# MPU6050.net
KiCad netlist of a schematic drawn in Altium Designer
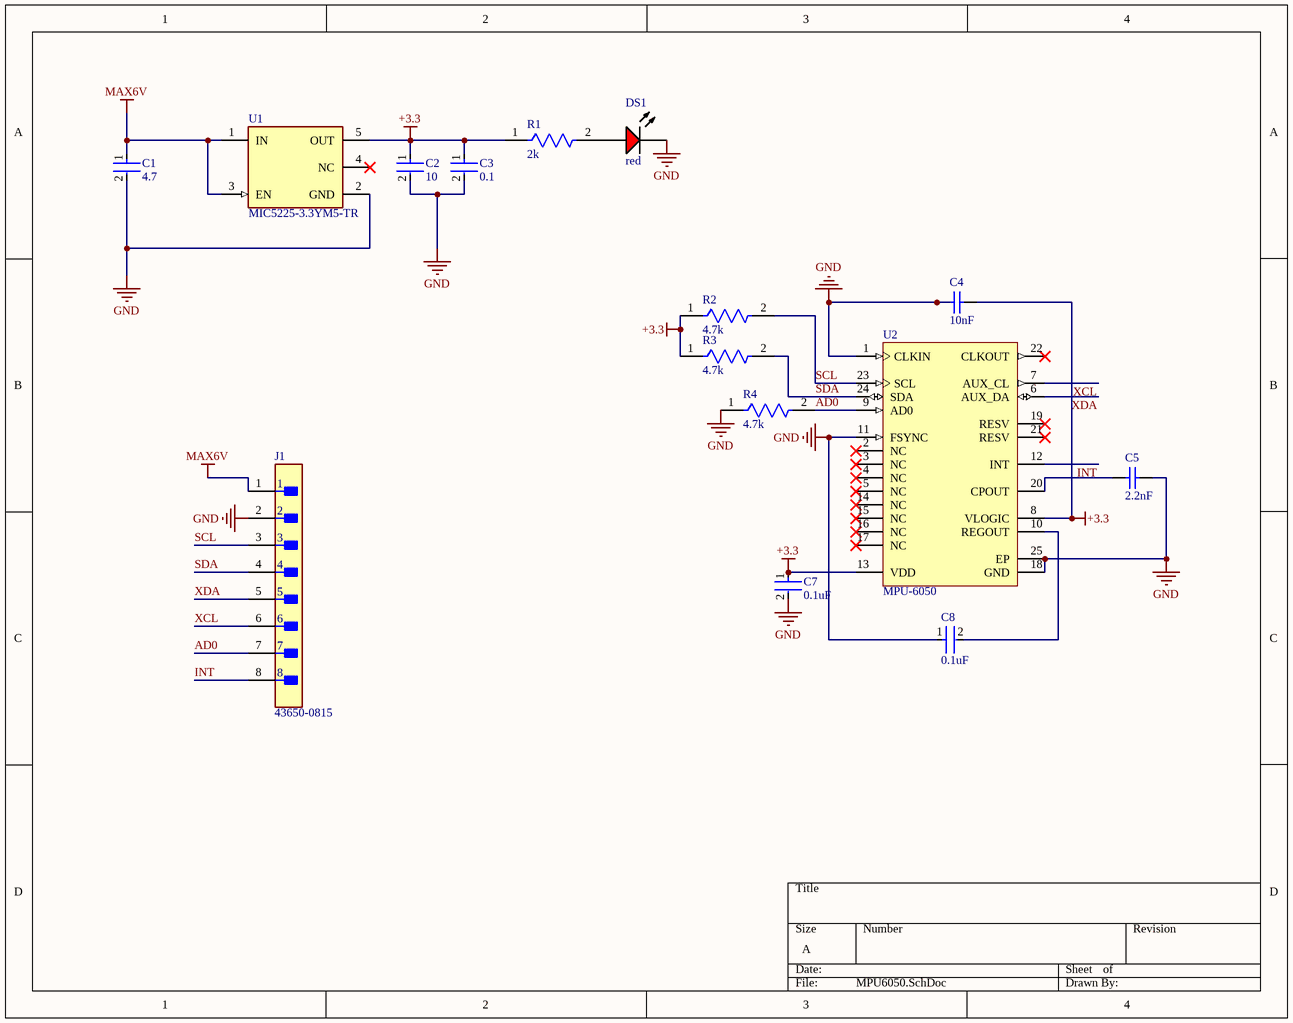
[diagram p0: MPU6050.SchDoc]

(export (version "E")
  (design (tool "Eeschema 10.0.6"))
  (components
    (comp (ref "C1")
      (value "4.7")
      (footprint "FP-C0805C475K8PACTU-MFG")
      (description "CAP CER 4.7UF 10V X5R 0805")
      (fields (field (name "TOLERANCE") "10%") (field (name "VOLTAGE") "10V"))
      (libsource (lib "Altium Content Vault") (part "e9c51b7dd13d4faca003ae77663ab08"))
    )
    (comp (ref "C2")
      (value "10")
      (footprint "FP-GRM21B-0_15-IPC_C")
      (description "Chip Multilayer Ceramic Capacitors for General Purpose, 0805, 10uF, X5R, 15%, 10%, 25V")
      (fields (field (name "VOLTAGE") "25V") (field (name "TOLERANCE") "10%"))
      (libsource (lib "Altium Content Vault") (part "b4654b650e69147ec39a6b967a45e02"))
    )
    (comp (ref "C3")
      (value "0.1")
      (footprint "FP-GCM155-0_05-IPC_C")
      (description "Ceramic Capacitor for Automotive 100nF ±10% 16VDC X7R 0402 Paper T/R")
      (fields (field (name "VOLTAGE") "16V") (field (name "TOLERANCE") "10%"))
      (libsource (lib "Altium Content Vault") (part "02cd4be3c70576c341d710602a673aa"))
    )
    (comp (ref "C4")
      (value "10nF")
      (footprint "CAPC0402(1005)60_M")
      (description "CAP 10nF 16V -20% to +80% 0402 (1005 Metric) Thickness 0.6mm SMD")
      (fields (field (name "TOLERANCE") "-20% to +80%"))
      (libsource (lib "Altium Content Vault") (part "CAP"))
    )
    (comp (ref "C5")
      (value "2.2nF")
      (footprint "CAPC1608X90X35NL10T15")
      (description "Chip Capacitor, 2.2 nF, +/- 10%, 50 V, -55 to 125 degC, 0603 (1608 Metric), RoHS, Tape and Reel")
      (fields (field (name "MANUFACTURER") "Murata"))
      (libsource (lib "Altium Content Vault") (part "CAP-NP-2"))
    )
    (comp (ref "C7")
      (value "0.1uF")
      (footprint "FP-GCM155-0_05-IPC_C")
      (description "Ceramic Capacitor for Automotive 100nF ±10% 16VDC X7R 0402 Paper T/R")
      (fields (field (name "VOLTAGE") "16V") (field (name "TOLERANCE") "10%"))
      (libsource (lib "Altium Content Vault") (part "02cd4be3c70576c341d710602a673aa"))
    )
    (comp (ref "C8")
      (value "0.1uF")
      (footprint "FP-GCM155-0_05-IPC_C")
      (description "Ceramic Capacitor for Automotive 100nF ±10% 16VDC X7R 0402 Paper T/R")
      (fields (field (name "VOLTAGE") "16V") (field (name "TOLERANCE") "10%"))
      (libsource (lib "Altium Content Vault") (part "02cd4be3c70576c341d710602a673aa"))
    )
    (comp (ref "DS1")
      (value "red")
      (footprint "VISH-TLMX1100_V")
      (description "LED, RED, 2.1 V, -40 to 100 degC, 2-Pin SMD (0603), RoHS, Tape and Reel")
      (fields (field (name "TOLERANCE") "5%"))
      (libsource (lib "Altium Content Vault") (part "LED-RED-AK-2"))
    )
    (comp (ref "J1")
      (value "43650-0815")
      (footprint "FP-43650-0815-MFG")
      (description "43650-0815 Conn Wire to Board HDR 8 POS 3mm Solder ST Top Entry Thru-Hole Micro-Fit 3.0™ Tray")
      (libsource (lib "Altium Content Vault") (part "99ec2b232beb5d2356d4d77f6a047f0"))
    )
    (comp (ref "R1")
      (value "2k")
      (footprint "FP-AC0603-IPC_B")
      (description "RES 2kΩ 1.00% 0.1W 0603")
      (fields (field (name "TOLERANCE") "1%"))
      (libsource (lib "Altium Content Vault") (part "1029c3af85768c4190bb7ad29bc67b5"))
    )
    (comp (ref "R2")
      (value "4.7k")
      (footprint "FP-CRCW0805-e3-IPC_B")
      (description "RES Thick Film, 4.7kΩ, 1%, 0.125W, 100ppm/°C, 0805")
      (fields (field (name "TOLERANCE") "1%"))
      (libsource (lib "Altium Content Vault") (part "1029c3af85768c4190bb7ad29bc67b5"))
    )
    (comp (ref "R3")
      (value "4.7k")
      (footprint "FP-CRCW0805-e3-IPC_B")
      (description "RES Thick Film, 4.7kΩ, 1%, 0.125W, 100ppm/°C, 0805")
      (fields (field (name "TOLERANCE") "1%"))
      (libsource (lib "Altium Content Vault") (part "1029c3af85768c4190bb7ad29bc67b5"))
    )
    (comp (ref "R4")
      (value "4.7k")
      (footprint "FP-CRCW0805-e3-IPC_B")
      (description "RES Thick Film, 4.7kΩ, 1%, 0.125W, 100ppm/°C, 0805")
      (fields (field (name "TOLERANCE") "1%"))
      (libsource (lib "Altium Content Vault") (part "1029c3af85768c4190bb7ad29bc67b5"))
    )
    (comp (ref "U1")
      (value "MIC5225-3.3YM5-TR")
      (footprint "FP-SOT23-5LD-PL-1-MFG")
      (description "IC REG LINEAR 3.3V 150MA SOT23-5")
      (fields
        (field (name "MANUFACTURER") "Microchip Technology")
        (field (name "OCTOPART") "https://octopart.com/mic5225-3.3ym5-tr-microchip-66802280")
      )
      (libsource (lib "Altium Content Vault") (part "19d222bb1c978341ac53d4d0acc2020"))
    )
    (comp (ref "U2")
      (value "MPU-6050")
      (footprint "IS-QFN-24_V")
      (fields (field (name "MANUFACTURER") "InvenSense"))
      (libsource (lib "Altium Content Vault") (part "IS-MPU-6050-QFN-24"))
    )
  )
  (nets
    (net (code "1") (name "+3.3") (class "Default")
      (node (ref "C2") (pin "1") (pinfunction "1_1") (pintype "passive"))
      (node (ref "C3") (pin "1") (pinfunction "1_1") (pintype "passive"))
      (node (ref "C4") (pin "1") (pinfunction "1_1") (pintype "passive"))
      (node (ref "C7") (pin "1") (pinfunction "1_1") (pintype "passive"))
      (node (ref "R1") (pin "1") (pinfunction "1_1") (pintype "passive"))
      (node (ref "R2") (pin "1") (pinfunction "1_1") (pintype "passive"))
      (node (ref "R3") (pin "1") (pinfunction "1_1") (pintype "passive"))
      (node (ref "U1") (pin "5") (pinfunction "OUT_5") (pintype "power_in"))
      (node (ref "U2") (pin "13") (pinfunction "VDD_13") (pintype "power_in"))
      (node (ref "U2") (pin "8") (pinfunction "VLOGIC_8") (pintype "power_in"))
    )
    (net (code "2") (name "/AD0") (class "Default")
      (node (ref "J1") (pin "7") (pinfunction "7_7") (pintype "passive"))
      (node (ref "R4") (pin "2") (pinfunction "2_2") (pintype "passive"))
      (node (ref "U2") (pin "9") (pinfunction "AD0_9") (pintype "input"))
    )
    (net (code "3") (name "/INT") (class "Default")
      (node (ref "J1") (pin "8") (pinfunction "8_8") (pintype "passive"))
      (node (ref "U2") (pin "12") (pinfunction "INT_12") (pintype "open_collector"))
    )
    (net (code "4") (name "/SCL") (class "Default")
      (node (ref "J1") (pin "3") (pinfunction "3_3") (pintype "passive"))
      (node (ref "R2") (pin "2") (pinfunction "2_2") (pintype "passive"))
      (node (ref "U2") (pin "23") (pinfunction "SCL_23") (pintype "input"))
    )
    (net (code "5") (name "/SDA") (class "Default")
      (node (ref "J1") (pin "4") (pinfunction "4_4") (pintype "passive"))
      (node (ref "R3") (pin "2") (pinfunction "2_2") (pintype "passive"))
      (node (ref "U2") (pin "24") (pinfunction "SDA_24") (pintype "bidirectional"))
    )
    (net (code "6") (name "/XCL") (class "Default")
      (node (ref "J1") (pin "6") (pinfunction "6_6") (pintype "passive"))
      (node (ref "U2") (pin "7") (pinfunction "AUX_CL_7") (pintype "output"))
    )
    (net (code "7") (name "/XDA") (class "Default")
      (node (ref "J1") (pin "5") (pinfunction "5_5") (pintype "passive"))
      (node (ref "U2") (pin "6") (pinfunction "AUX_DA_6") (pintype "bidirectional"))
    )
    (net (code "8") (name "GND") (class "Default")
      (node (ref "C1") (pin "2") (pinfunction "2_2") (pintype "passive"))
      (node (ref "C2") (pin "2") (pinfunction "2_2") (pintype "passive"))
      (node (ref "C3") (pin "2") (pinfunction "2_2") (pintype "passive"))
      (node (ref "C4") (pin "2") (pinfunction "2_2") (pintype "passive"))
      (node (ref "C5") (pin "2") (pinfunction "2_2") (pintype "passive"))
      (node (ref "C7") (pin "2") (pinfunction "2_2") (pintype "passive"))
      (node (ref "C8") (pin "1") (pinfunction "1_1") (pintype "passive"))
      (node (ref "DS1") (pin "2") (pinfunction "K_2") (pintype "passive"))
      (node (ref "J1") (pin "2") (pinfunction "2_2") (pintype "passive"))
      (node (ref "R4") (pin "1") (pinfunction "1_1") (pintype "passive"))
      (node (ref "U1") (pin "2") (pinfunction "GND_2") (pintype "power_in"))
      (node (ref "U2") (pin "1") (pinfunction "CLKIN_1") (pintype "input"))
      (node (ref "U2") (pin "11") (pinfunction "FSYNC_11") (pintype "input"))
      (node (ref "U2") (pin "18") (pinfunction "GND_18") (pintype "power_in"))
      (node (ref "U2") (pin "25") (pinfunction "EP_25") (pintype "power_in"))
    )
    (net (code "9") (name "MAX6V") (class "Default")
      (node (ref "C1") (pin "1") (pinfunction "1_1") (pintype "passive"))
      (node (ref "J1") (pin "1") (pinfunction "1_1") (pintype "passive"))
      (node (ref "U1") (pin "1") (pinfunction "IN_1") (pintype "power_in"))
      (node (ref "U1") (pin "3") (pinfunction "EN_3") (pintype "input"))
    )
    (net (code "10") (name "Net-(DS1-A)") (class "Default")
      (node (ref "DS1") (pin "1") (pinfunction "A_1") (pintype "passive"))
      (node (ref "R1") (pin "2") (pinfunction "2_2") (pintype "passive"))
    )
    (net (code "11") (name "Net-(U2-CPOUT)") (class "Default")
      (node (ref "C5") (pin "1") (pinfunction "1_1") (pintype "passive"))
      (node (ref "U2") (pin "20") (pinfunction "CPOUT_20") (pintype "passive"))
    )
    (net (code "12") (name "Net-(U2-REGOUT)") (class "Default")
      (node (ref "C8") (pin "2") (pinfunction "2_2") (pintype "passive"))
      (node (ref "U2") (pin "10") (pinfunction "REGOUT_10") (pintype "passive"))
    )
    (net (code "13") (name "unconnected-(U1-NC-Pad4)") (class "Default")
      (node (ref "U1") (pin "4") (pinfunction "NC_4") (pintype "passive+no_connect"))
    )
    (net (code "14") (name "unconnected-(U2-CLKOUT-Pad22)") (class "Default")
      (node (ref "U2") (pin "22") (pinfunction "CLKOUT_22") (pintype "output+no_connect"))
    )
    (net (code "15") (name "unconnected-(U2-NC-Pad2)") (class "Default")
      (node (ref "U2") (pin "2") (pinfunction "NC_2") (pintype "passive+no_connect"))
    )
    (net (code "16") (name "unconnected-(U2-NC-Pad3)") (class "Default")
      (node (ref "U2") (pin "3") (pinfunction "NC_3") (pintype "passive+no_connect"))
    )
    (net (code "17") (name "unconnected-(U2-NC-Pad4)") (class "Default")
      (node (ref "U2") (pin "4") (pinfunction "NC_4") (pintype "passive+no_connect"))
    )
    (net (code "18") (name "unconnected-(U2-NC-Pad5)") (class "Default")
      (node (ref "U2") (pin "5") (pinfunction "NC_5") (pintype "passive+no_connect"))
    )
    (net (code "19") (name "unconnected-(U2-NC-Pad14)") (class "Default")
      (node (ref "U2") (pin "14") (pinfunction "NC_14") (pintype "passive+no_connect"))
    )
    (net (code "20") (name "unconnected-(U2-NC-Pad15)") (class "Default")
      (node (ref "U2") (pin "15") (pinfunction "NC_15") (pintype "passive+no_connect"))
    )
    (net (code "21") (name "unconnected-(U2-NC-Pad16)") (class "Default")
      (node (ref "U2") (pin "16") (pinfunction "NC_16") (pintype "passive+no_connect"))
    )
    (net (code "22") (name "unconnected-(U2-NC-Pad17)") (class "Default")
      (node (ref "U2") (pin "17") (pinfunction "NC_17") (pintype "passive+no_connect"))
    )
    (net (code "23") (name "unconnected-(U2-RESV-Pad19)") (class "Default")
      (node (ref "U2") (pin "19") (pinfunction "RESV_19") (pintype "passive+no_connect"))
    )
    (net (code "24") (name "unconnected-(U2-RESV-Pad21)") (class "Default")
      (node (ref "U2") (pin "21") (pinfunction "RESV_21") (pintype "passive+no_connect"))
    )
  )
)
